# eeprom_burner.net
KiCad netlist of a schematic drawn in EAGLE
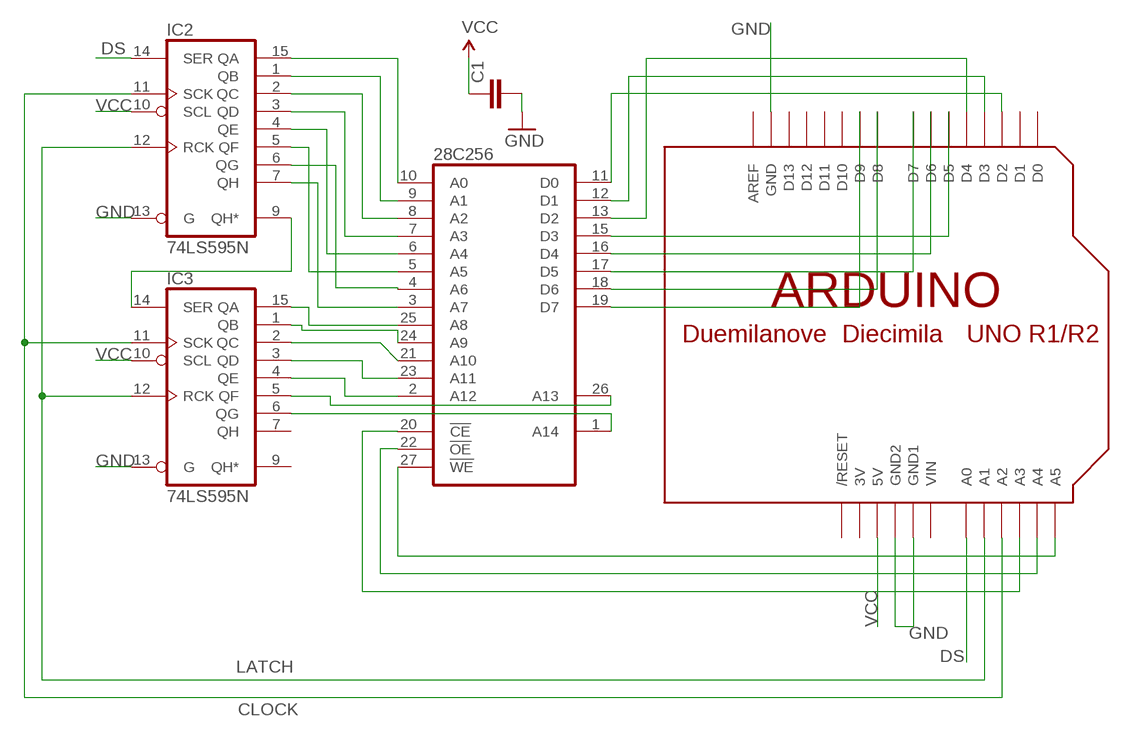
[diagram p0: schematic, sheet 1]

(export (version "E")
  (design (tool "Eeschema 10.0.6"))
  (components
    (comp (ref "28C256")
      (value "2864")
      (footprint "eagle-import:DIL28")
      (libsource (lib "eagle-import") (part "2864"))
    )
    (comp (ref "C1")
      (value "CAPPTH")
      (footprint "eagle-import:CAP-PTH-SMALL")
      (libsource (lib "eagle-import") (part "CAPPTH"))
    )
    (comp (ref "IC2")
      (value "74LS595N")
      (footprint "eagle-import:DIL16")
      (libsource (lib "eagle-import") (part "74595NLS"))
    )
    (comp (ref "IC3")
      (value "74LS595N")
      (footprint "eagle-import:DIL16")
      (libsource (lib "eagle-import") (part "74595NLS"))
    )
    (comp (ref "U$1")
      (value "ARDUINOUNO")
      (footprint "eagle-import:ARDUINO")
      (libsource (lib "eagle-import") (part "ARDUINOUNO"))
    )
  )
  (nets
    (net (code "1") (name "/3V") (class "Default")
      (node (ref "U$1") (pin "3V") (pinfunction "3V_3V") (pintype "power_in"))
    )
    (net (code "2") (name "/CLOCK") (class "Default")
      (node (ref "IC2") (pin "11") (pinfunction "SCK_11") (pintype "input"))
      (node (ref "IC3") (pin "11") (pinfunction "SCK_11") (pintype "input"))
      (node (ref "U$1") (pin "A2") (pinfunction "A2_A2") (pintype "bidirectional"))
    )
    (net (code "3") (name "/DS") (class "Default")
      (node (ref "IC2") (pin "14") (pinfunction "SER_14") (pintype "input"))
      (node (ref "U$1") (pin "A0") (pinfunction "A0_A0") (pintype "bidirectional"))
    )
    (net (code "4") (name "/LATCH") (class "Default")
      (node (ref "IC2") (pin "12") (pinfunction "RCK_12") (pintype "input"))
      (node (ref "IC3") (pin "12") (pinfunction "RCK_12") (pintype "input"))
      (node (ref "U$1") (pin "A1") (pinfunction "A1_A1") (pintype "bidirectional"))
    )
    (net (code "5") (name "/VIN") (class "Default")
      (node (ref "U$1") (pin "VIN") (pinfunction "VIN_VIN") (pintype "power_in"))
    )
    (net (code "6") (name "GND") (class "Default")
      (node (ref "C1") (pin "2") (pinfunction "2_2") (pintype "passive"))
      (node (ref "IC2") (pin "13") (pinfunction "G_13") (pintype "input"))
      (node (ref "IC3") (pin "13") (pinfunction "G_13") (pintype "input"))
      (node (ref "U$1") (pin "GND") (pinfunction "GND_GND") (pintype "power_in"))
      (node (ref "U$1") (pin "GND1") (pinfunction "GND1_GND1") (pintype "power_in"))
      (node (ref "U$1") (pin "GND2") (pinfunction "GND2_GND2") (pintype "power_in"))
    )
    (net (code "7") (name "Net-(28C256A-A0)") (class "Default")
      (node (ref "28C256") (pin "10") (pinfunction "A0_10") (pintype "input"))
      (node (ref "IC2") (pin "15") (pinfunction "QA_15") (pintype "tri_state"))
    )
    (net (code "8") (name "Net-(28C256A-A1)") (class "Default")
      (node (ref "28C256") (pin "9") (pinfunction "A1_9") (pintype "input"))
      (node (ref "IC2") (pin "1") (pinfunction "QB_1") (pintype "tri_state"))
    )
    (net (code "9") (name "Net-(28C256A-A2)") (class "Default")
      (node (ref "28C256") (pin "8") (pinfunction "A2_8") (pintype "input"))
      (node (ref "IC2") (pin "2") (pinfunction "QC_2") (pintype "tri_state"))
    )
    (net (code "10") (name "Net-(28C256A-A3)") (class "Default")
      (node (ref "28C256") (pin "7") (pinfunction "A3_7") (pintype "input"))
      (node (ref "IC2") (pin "3") (pinfunction "QD_3") (pintype "tri_state"))
    )
    (net (code "11") (name "Net-(28C256A-A4)") (class "Default")
      (node (ref "28C256") (pin "6") (pinfunction "A4_6") (pintype "input"))
      (node (ref "IC2") (pin "4") (pinfunction "QE_4") (pintype "tri_state"))
    )
    (net (code "12") (name "Net-(28C256A-A5)") (class "Default")
      (node (ref "28C256") (pin "5") (pinfunction "A5_5") (pintype "input"))
      (node (ref "IC2") (pin "5") (pinfunction "QF_5") (pintype "tri_state"))
    )
    (net (code "13") (name "Net-(28C256A-A6)") (class "Default")
      (node (ref "28C256") (pin "4") (pinfunction "A6_4") (pintype "input"))
      (node (ref "IC2") (pin "6") (pinfunction "QG_6") (pintype "tri_state"))
    )
    (net (code "14") (name "Net-(28C256A-A7)") (class "Default")
      (node (ref "28C256") (pin "3") (pinfunction "A7_3") (pintype "input"))
      (node (ref "IC2") (pin "7") (pinfunction "QH_7") (pintype "tri_state"))
    )
    (net (code "15") (name "Net-(28C256A-A8)") (class "Default")
      (node (ref "28C256") (pin "25") (pinfunction "A8_25") (pintype "input"))
      (node (ref "IC3") (pin "15") (pinfunction "QA_15") (pintype "tri_state"))
    )
    (net (code "16") (name "Net-(28C256A-A9)") (class "Default")
      (node (ref "28C256") (pin "24") (pinfunction "A9_24") (pintype "input"))
      (node (ref "IC3") (pin "1") (pinfunction "QB_1") (pintype "tri_state"))
    )
    (net (code "17") (name "Net-(28C256A-A10)") (class "Default")
      (node (ref "28C256") (pin "21") (pinfunction "A10_21") (pintype "input"))
      (node (ref "IC3") (pin "2") (pinfunction "QC_2") (pintype "tri_state"))
    )
    (net (code "18") (name "Net-(28C256A-A11)") (class "Default")
      (node (ref "28C256") (pin "23") (pinfunction "A11_23") (pintype "input"))
      (node (ref "IC3") (pin "3") (pinfunction "QD_3") (pintype "tri_state"))
    )
    (net (code "19") (name "Net-(28C256A-A12)") (class "Default")
      (node (ref "28C256") (pin "2") (pinfunction "A12_2") (pintype "input"))
      (node (ref "IC3") (pin "4") (pinfunction "QE_4") (pintype "tri_state"))
    )
    (net (code "20") (name "Net-(28C256A-A13)") (class "Default")
      (node (ref "28C256") (pin "26") (pinfunction "A13_26") (pintype "input"))
      (node (ref "IC3") (pin "5") (pinfunction "QF_5") (pintype "tri_state"))
    )
    (net (code "21") (name "Net-(28C256A-A14)") (class "Default")
      (node (ref "28C256") (pin "1") (pinfunction "A14_1") (pintype "input"))
      (node (ref "IC3") (pin "6") (pinfunction "QG_6") (pintype "tri_state"))
    )
    (net (code "22") (name "Net-(28C256A-D0)") (class "Default")
      (node (ref "28C256") (pin "11") (pinfunction "D0_11") (pintype "bidirectional"))
      (node (ref "U$1") (pin "D2") (pinfunction "D2_D2") (pintype "bidirectional"))
    )
    (net (code "23") (name "Net-(28C256A-D1)") (class "Default")
      (node (ref "28C256") (pin "12") (pinfunction "D1_12") (pintype "bidirectional"))
      (node (ref "U$1") (pin "D3") (pinfunction "D3_D3") (pintype "bidirectional"))
    )
    (net (code "24") (name "Net-(28C256A-D2)") (class "Default")
      (node (ref "28C256") (pin "13") (pinfunction "D2_13") (pintype "bidirectional"))
      (node (ref "U$1") (pin "D4") (pinfunction "D4_D4") (pintype "bidirectional"))
    )
    (net (code "25") (name "Net-(28C256A-D3)") (class "Default")
      (node (ref "28C256") (pin "15") (pinfunction "D3_15") (pintype "bidirectional"))
      (node (ref "U$1") (pin "D5") (pinfunction "D5_D5") (pintype "bidirectional"))
    )
    (net (code "26") (name "Net-(28C256A-D4)") (class "Default")
      (node (ref "28C256") (pin "16") (pinfunction "D4_16") (pintype "bidirectional"))
      (node (ref "U$1") (pin "D6") (pinfunction "D6_D6") (pintype "bidirectional"))
    )
    (net (code "27") (name "Net-(28C256A-D5)") (class "Default")
      (node (ref "28C256") (pin "17") (pinfunction "D5_17") (pintype "bidirectional"))
      (node (ref "U$1") (pin "D7") (pinfunction "D7_D7") (pintype "bidirectional"))
    )
    (net (code "28") (name "Net-(28C256A-D6)") (class "Default")
      (node (ref "28C256") (pin "18") (pinfunction "D6_18") (pintype "bidirectional"))
      (node (ref "U$1") (pin "D8") (pinfunction "D8_D8") (pintype "bidirectional"))
    )
    (net (code "29") (name "Net-(28C256A-D7)") (class "Default")
      (node (ref "28C256") (pin "19") (pinfunction "D7_19") (pintype "bidirectional"))
      (node (ref "U$1") (pin "D9") (pinfunction "D9_D9") (pintype "bidirectional"))
    )
    (net (code "30") (name "Net-(28C256A-~{CE})") (class "Default")
      (node (ref "28C256") (pin "20") (pinfunction "~{CE}_20") (pintype "input"))
      (node (ref "U$1") (pin "A3") (pinfunction "A3_A3") (pintype "bidirectional"))
    )
    (net (code "31") (name "Net-(28C256A-~{OE})") (class "Default")
      (node (ref "28C256") (pin "22") (pinfunction "~{OE}_22") (pintype "input"))
      (node (ref "U$1") (pin "A4") (pinfunction "A4_A4") (pintype "bidirectional"))
    )
    (net (code "32") (name "Net-(28C256A-~{WE})") (class "Default")
      (node (ref "28C256") (pin "27") (pinfunction "~{WE}_27") (pintype "input"))
      (node (ref "U$1") (pin "A5") (pinfunction "A5_A5") (pintype "bidirectional"))
    )
    (net (code "33") (name "Net-(IC2A-QH*)") (class "Default")
      (node (ref "IC2") (pin "9") (pinfunction "QH*_9") (pintype "tri_state"))
      (node (ref "IC3") (pin "14") (pinfunction "SER_14") (pintype "input"))
    )
    (net (code "34") (name "VCC") (class "Default")
      (node (ref "C1") (pin "1") (pinfunction "1_1") (pintype "passive"))
      (node (ref "IC2") (pin "10") (pinfunction "SCL_10") (pintype "input"))
      (node (ref "IC3") (pin "10") (pinfunction "SCL_10") (pintype "input"))
      (node (ref "U$1") (pin "5V") (pinfunction "5V_5V") (pintype "power_in"))
    )
    (net (code "35") (name "unconnected-(IC3A-QH*-Pad9)") (class "Default")
      (node (ref "IC3") (pin "9") (pinfunction "QH*_9") (pintype "tri_state"))
    )
    (net (code "36") (name "unconnected-(IC3A-QH-Pad7)") (class "Default")
      (node (ref "IC3") (pin "7") (pinfunction "QH_7") (pintype "tri_state"))
    )
    (net (code "37") (name "unconnected-(U$1-PadAREF)") (class "Default")
      (node (ref "U$1") (pin "AREF") (pinfunction "AREF_AREF") (pintype "bidirectional"))
    )
    (net (code "38") (name "unconnected-(U$1-PadD0)") (class "Default")
      (node (ref "U$1") (pin "D0") (pinfunction "D0_D0") (pintype "bidirectional"))
    )
    (net (code "39") (name "unconnected-(U$1-PadD1)") (class "Default")
      (node (ref "U$1") (pin "D1") (pinfunction "D1_D1") (pintype "bidirectional"))
    )
    (net (code "40") (name "unconnected-(U$1-PadD10)") (class "Default")
      (node (ref "U$1") (pin "D10") (pinfunction "D10_D10") (pintype "bidirectional"))
    )
    (net (code "41") (name "unconnected-(U$1-PadD11)") (class "Default")
      (node (ref "U$1") (pin "D11") (pinfunction "D11_D11") (pintype "bidirectional"))
    )
    (net (code "42") (name "unconnected-(U$1-PadD12)") (class "Default")
      (node (ref "U$1") (pin "D12") (pinfunction "D12_D12") (pintype "bidirectional"))
    )
    (net (code "43") (name "unconnected-(U$1-PadD13)") (class "Default")
      (node (ref "U$1") (pin "D13") (pinfunction "D13_D13") (pintype "bidirectional"))
    )
    (net (code "44") (name "unconnected-(U$1-{slash}RESET-PadRESET)") (class "Default")
      (node (ref "U$1") (pin "RESET") (pinfunction "/RESET_RESET") (pintype "bidirectional"))
    )
  )
)
